# limit_switches.net
KiCad netlist of a schematic drawn in Altium Designer
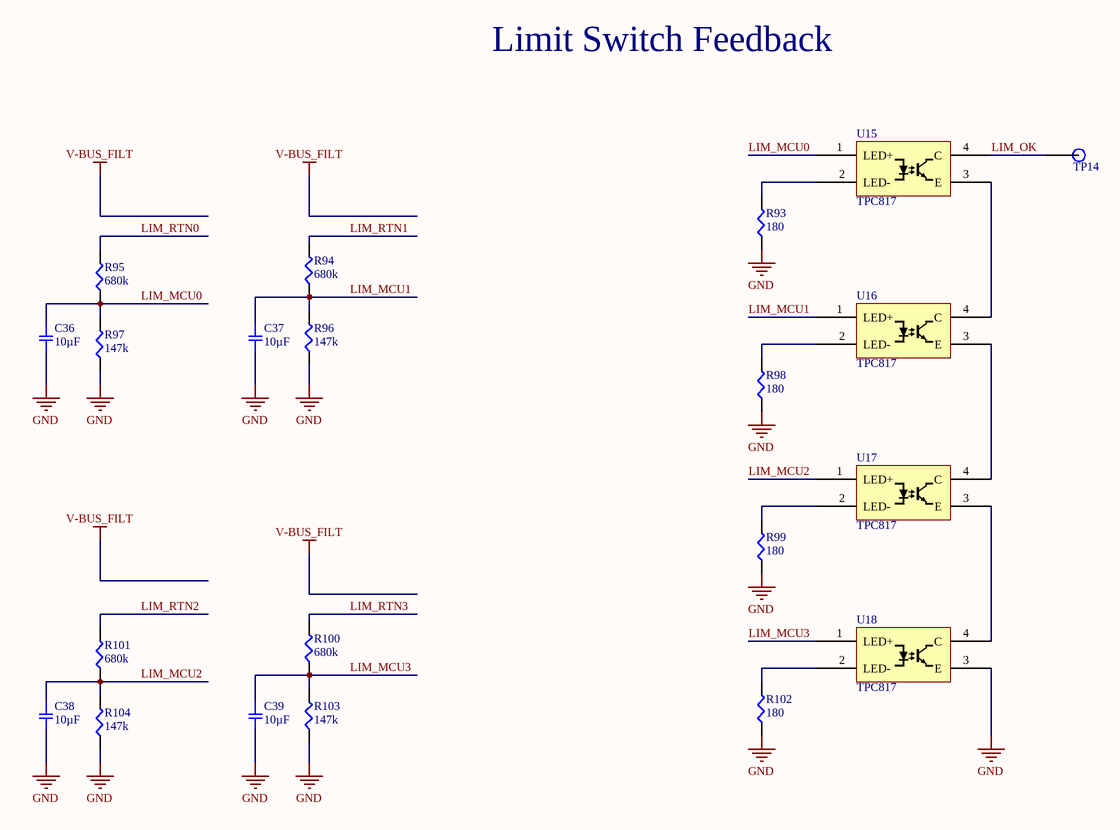
[diagram p0: limit_switches.SchDoc]

(export (version "E")
  (design (tool "Eeschema 10.0.6"))
  (components
    (comp (ref "C36")
      (value "10µF")
      (footprint "SMD-0805C")
      (description "CAP CER 10UF 25V X6S 0805")
      (fields
        (field (name "DIGI-KEY PART NUMBER") "490-10502-1-ND")
        (field (name "PART NUMBER") "GRM21BC81E106KE51L")
      )
      (libsource (lib "capacitor") (part "GRM21BC81E106KE51L"))
    )
    (comp (ref "C37")
      (value "10µF")
      (footprint "SMD-0805C")
      (description "CAP CER 10UF 25V X6S 0805")
      (fields
        (field (name "DIGI-KEY PART NUMBER") "490-10502-1-ND")
        (field (name "PART NUMBER") "GRM21BC81E106KE51L")
      )
      (libsource (lib "capacitor") (part "GRM21BC81E106KE51L"))
    )
    (comp (ref "C38")
      (value "10µF")
      (footprint "SMD-0805C")
      (description "CAP CER 10UF 25V X6S 0805")
      (fields
        (field (name "DIGI-KEY PART NUMBER") "490-10502-1-ND")
        (field (name "PART NUMBER") "GRM21BC81E106KE51L")
      )
      (libsource (lib "capacitor") (part "GRM21BC81E106KE51L"))
    )
    (comp (ref "C39")
      (value "10µF")
      (footprint "SMD-0805C")
      (description "CAP CER 10UF 25V X6S 0805")
      (fields
        (field (name "DIGI-KEY PART NUMBER") "490-10502-1-ND")
        (field (name "PART NUMBER") "GRM21BC81E106KE51L")
      )
      (libsource (lib "capacitor") (part "GRM21BC81E106KE51L"))
    )
    (comp (ref "R93")
      (value "180")
      (footprint "SMD-0805-RES")
      (description "RES SMD 180 OHM 1% 1/8W 0805")
      (fields (field (name "PART NUMBER") "ERJ-6ENF1800V") (field (name "DIGI-KEY PART NUMBER") "P180CCT-ND"))
      (libsource (lib "resistors") (part "ERJ-6ENF1800V"))
    )
    (comp (ref "R94")
      (value "680k")
      (footprint "SMD-0805-RES")
      (description "RES SMD 680K OHM 1% 1/8W 0805")
      (fields
        (field (name "PART NUMBER") "ERJ-6ENF6803V")
        (field (name "DIGI-KEY PART NUMBER") "P680KCCT-ND")
      )
      (libsource (lib "resistors") (part "ERJ-6ENF6803V"))
    )
    (comp (ref "R95")
      (value "680k")
      (footprint "SMD-0805-RES")
      (description "RES SMD 680K OHM 1% 1/8W 0805")
      (fields
        (field (name "PART NUMBER") "ERJ-6ENF6803V")
        (field (name "DIGI-KEY PART NUMBER") "P680KCCT-ND")
      )
      (libsource (lib "resistors") (part "ERJ-6ENF6803V"))
    )
    (comp (ref "R96")
      (value "147k")
      (footprint "SMD-0805-RES")
      (description "RES SMD 147K OHM 1% 1/8W 0805")
      (fields
        (field (name "PART NUMBER") "ERJ-6ENF1473V")
        (field (name "DIGI-KEY PART NUMBER") "P147KCCT-ND")
      )
      (libsource (lib "resistors") (part "ERJ-6ENF1473V"))
    )
    (comp (ref "R97")
      (value "147k")
      (footprint "SMD-0805-RES")
      (description "RES SMD 147K OHM 1% 1/8W 0805")
      (fields
        (field (name "PART NUMBER") "ERJ-6ENF1473V")
        (field (name "DIGI-KEY PART NUMBER") "P147KCCT-ND")
      )
      (libsource (lib "resistors") (part "ERJ-6ENF1473V"))
    )
    (comp (ref "R98")
      (value "180")
      (footprint "SMD-0805-RES")
      (description "RES SMD 180 OHM 1% 1/8W 0805")
      (fields (field (name "PART NUMBER") "ERJ-6ENF1800V") (field (name "DIGI-KEY PART NUMBER") "P180CCT-ND"))
      (libsource (lib "resistors") (part "ERJ-6ENF1800V"))
    )
    (comp (ref "R99")
      (value "180")
      (footprint "SMD-0805-RES")
      (description "RES SMD 180 OHM 1% 1/8W 0805")
      (fields (field (name "PART NUMBER") "ERJ-6ENF1800V") (field (name "DIGI-KEY PART NUMBER") "P180CCT-ND"))
      (libsource (lib "resistors") (part "ERJ-6ENF1800V"))
    )
    (comp (ref "R100")
      (value "680k")
      (footprint "SMD-0805-RES")
      (description "RES SMD 680K OHM 1% 1/8W 0805")
      (fields
        (field (name "PART NUMBER") "ERJ-6ENF6803V")
        (field (name "DIGI-KEY PART NUMBER") "P680KCCT-ND")
      )
      (libsource (lib "resistors") (part "ERJ-6ENF6803V"))
    )
    (comp (ref "R101")
      (value "680k")
      (footprint "SMD-0805-RES")
      (description "RES SMD 680K OHM 1% 1/8W 0805")
      (fields
        (field (name "PART NUMBER") "ERJ-6ENF6803V")
        (field (name "DIGI-KEY PART NUMBER") "P680KCCT-ND")
      )
      (libsource (lib "resistors") (part "ERJ-6ENF6803V"))
    )
    (comp (ref "R102")
      (value "180")
      (footprint "SMD-0805-RES")
      (description "RES SMD 180 OHM 1% 1/8W 0805")
      (fields (field (name "PART NUMBER") "ERJ-6ENF1800V") (field (name "DIGI-KEY PART NUMBER") "P180CCT-ND"))
      (libsource (lib "resistors") (part "ERJ-6ENF1800V"))
    )
    (comp (ref "R103")
      (value "147k")
      (footprint "SMD-0805-RES")
      (description "RES SMD 147K OHM 1% 1/8W 0805")
      (fields
        (field (name "PART NUMBER") "ERJ-6ENF1473V")
        (field (name "DIGI-KEY PART NUMBER") "P147KCCT-ND")
      )
      (libsource (lib "resistors") (part "ERJ-6ENF1473V"))
    )
    (comp (ref "R104")
      (value "147k")
      (footprint "SMD-0805-RES")
      (description "RES SMD 147K OHM 1% 1/8W 0805")
      (fields
        (field (name "PART NUMBER") "ERJ-6ENF1473V")
        (field (name "DIGI-KEY PART NUMBER") "P147KCCT-ND")
      )
      (libsource (lib "resistors") (part "ERJ-6ENF1473V"))
    )
    (comp (ref "TP14")
      (value "TP")
      (footprint "Test Point")
      (description "SMD TEST POINT")
      (libsource (lib "misc") (part "TP"))
    )
    (comp (ref "U15")
      (value "TPC817")
      (footprint "SOT200P1005X328-5N")
      (description "OPTOISO 5KV TRANS 4SOP")
      (fields (field (name "MANUFACTURER") "Taiwan Semi"))
      (libsource (lib "ic") (part "TPC817"))
    )
    (comp (ref "U16")
      (value "TPC817")
      (footprint "SOT200P1005X328-5N")
      (description "OPTOISO 5KV TRANS 4SOP")
      (fields (field (name "MANUFACTURER") "Taiwan Semi"))
      (libsource (lib "ic") (part "TPC817"))
    )
    (comp (ref "U17")
      (value "TPC817")
      (footprint "SOT200P1005X328-5N")
      (description "OPTOISO 5KV TRANS 4SOP")
      (fields (field (name "MANUFACTURER") "Taiwan Semi"))
      (libsource (lib "ic") (part "TPC817"))
    )
    (comp (ref "U18")
      (value "TPC817")
      (footprint "SOT200P1005X328-5N")
      (description "OPTOISO 5KV TRANS 4SOP")
      (fields (field (name "MANUFACTURER") "Taiwan Semi"))
      (libsource (lib "ic") (part "TPC817"))
    )
  )
  (nets
    (net (code "1") (name "/LIM_MCU0") (class "Default")
      (node (ref "C36") (pin "1") (pinfunction "1_1") (pintype "passive"))
      (node (ref "R95") (pin "1") (pinfunction "1_1") (pintype "passive"))
      (node (ref "R97") (pin "2") (pinfunction "2_2") (pintype "passive"))
      (node (ref "U15") (pin "1") (pinfunction "LED+_1") (pintype "passive"))
    )
    (net (code "2") (name "/LIM_MCU1") (class "Default")
      (node (ref "C37") (pin "1") (pinfunction "1_1") (pintype "passive"))
      (node (ref "R94") (pin "1") (pinfunction "1_1") (pintype "passive"))
      (node (ref "R96") (pin "2") (pinfunction "2_2") (pintype "passive"))
      (node (ref "U16") (pin "1") (pinfunction "LED+_1") (pintype "passive"))
    )
    (net (code "3") (name "/LIM_MCU2") (class "Default")
      (node (ref "C38") (pin "1") (pinfunction "1_1") (pintype "passive"))
      (node (ref "R101") (pin "1") (pinfunction "1_1") (pintype "passive"))
      (node (ref "R104") (pin "2") (pinfunction "2_2") (pintype "passive"))
      (node (ref "U17") (pin "1") (pinfunction "LED+_1") (pintype "passive"))
    )
    (net (code "4") (name "/LIM_MCU3") (class "Default")
      (node (ref "C39") (pin "1") (pinfunction "1_1") (pintype "passive"))
      (node (ref "R100") (pin "1") (pinfunction "1_1") (pintype "passive"))
      (node (ref "R103") (pin "2") (pinfunction "2_2") (pintype "passive"))
      (node (ref "U18") (pin "1") (pinfunction "LED+_1") (pintype "passive"))
    )
    (net (code "5") (name "/LIM_OK") (class "Default")
      (node (ref "TP14") (pin "1") (pinfunction "1_1") (pintype "passive"))
      (node (ref "U15") (pin "4") (pinfunction "C_4") (pintype "passive"))
    )
    (net (code "6") (name "/LIM_RTN0") (class "Default")
      (node (ref "R95") (pin "2") (pinfunction "2_2") (pintype "passive"))
    )
    (net (code "7") (name "/LIM_RTN1") (class "Default")
      (node (ref "R94") (pin "2") (pinfunction "2_2") (pintype "passive"))
    )
    (net (code "8") (name "/LIM_RTN2") (class "Default")
      (node (ref "R101") (pin "2") (pinfunction "2_2") (pintype "passive"))
    )
    (net (code "9") (name "/LIM_RTN3") (class "Default")
      (node (ref "R100") (pin "2") (pinfunction "2_2") (pintype "passive"))
    )
    (net (code "10") (name "GND") (class "Default")
      (node (ref "C36") (pin "2") (pinfunction "2_2") (pintype "passive"))
      (node (ref "C37") (pin "2") (pinfunction "2_2") (pintype "passive"))
      (node (ref "C38") (pin "2") (pinfunction "2_2") (pintype "passive"))
      (node (ref "C39") (pin "2") (pinfunction "2_2") (pintype "passive"))
      (node (ref "R102") (pin "1") (pinfunction "1_1") (pintype "passive"))
      (node (ref "R103") (pin "1") (pinfunction "1_1") (pintype "passive"))
      (node (ref "R104") (pin "1") (pinfunction "1_1") (pintype "passive"))
      (node (ref "R93") (pin "1") (pinfunction "1_1") (pintype "passive"))
      (node (ref "R96") (pin "1") (pinfunction "1_1") (pintype "passive"))
      (node (ref "R97") (pin "1") (pinfunction "1_1") (pintype "passive"))
      (node (ref "R98") (pin "1") (pinfunction "1_1") (pintype "passive"))
      (node (ref "R99") (pin "1") (pinfunction "1_1") (pintype "passive"))
      (node (ref "U18") (pin "3") (pinfunction "E_3") (pintype "passive"))
    )
    (net (code "11") (name "Net-(U15-E)") (class "Default")
      (node (ref "U15") (pin "3") (pinfunction "E_3") (pintype "passive"))
      (node (ref "U16") (pin "4") (pinfunction "C_4") (pintype "passive"))
    )
    (net (code "12") (name "Net-(U15-LED-)") (class "Default")
      (node (ref "R93") (pin "2") (pinfunction "2_2") (pintype "passive"))
      (node (ref "U15") (pin "2") (pinfunction "LED-_2") (pintype "passive"))
    )
    (net (code "13") (name "Net-(U16-E)") (class "Default")
      (node (ref "U16") (pin "3") (pinfunction "E_3") (pintype "passive"))
      (node (ref "U17") (pin "4") (pinfunction "C_4") (pintype "passive"))
    )
    (net (code "14") (name "Net-(U16-LED-)") (class "Default")
      (node (ref "R98") (pin "2") (pinfunction "2_2") (pintype "passive"))
      (node (ref "U16") (pin "2") (pinfunction "LED-_2") (pintype "passive"))
    )
    (net (code "15") (name "Net-(U17-E)") (class "Default")
      (node (ref "U17") (pin "3") (pinfunction "E_3") (pintype "passive"))
      (node (ref "U18") (pin "4") (pinfunction "C_4") (pintype "passive"))
    )
    (net (code "16") (name "Net-(U17-LED-)") (class "Default")
      (node (ref "R99") (pin "2") (pinfunction "2_2") (pintype "passive"))
      (node (ref "U17") (pin "2") (pinfunction "LED-_2") (pintype "passive"))
    )
    (net (code "17") (name "Net-(U18-LED-)") (class "Default")
      (node (ref "R102") (pin "2") (pinfunction "2_2") (pintype "passive"))
      (node (ref "U18") (pin "2") (pinfunction "LED-_2") (pintype "passive"))
    )
  )
)
